# 5VAC-DC.net
KiCad netlist of a schematic drawn in EAGLE
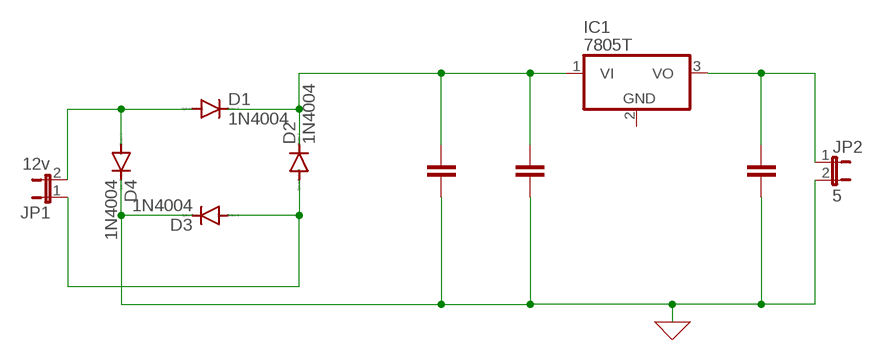
[diagram p0: schematic, sheet 1]

(export (version "E")
  (design (tool "Eeschema 10.0.6"))
  (components
    (comp (ref "D1")
      (value "1N4004")
      (footprint "eagle-import:DO41-10")
      (libsource (lib "eagle-import") (part "1N4004"))
    )
    (comp (ref "D2")
      (value "1N4004")
      (footprint "eagle-import:DO41-10")
      (libsource (lib "eagle-import") (part "1N4004"))
    )
    (comp (ref "D3")
      (value "1N4004")
      (footprint "eagle-import:DO41-10")
      (libsource (lib "eagle-import") (part "1N4004"))
    )
    (comp (ref "D4")
      (value "1N4004")
      (footprint "eagle-import:DO41-10")
      (libsource (lib "eagle-import") (part "1N4004"))
    )
    (comp (ref "IC1")
      (value "7805T")
      (footprint "eagle-import:TO220H")
      (libsource (lib "eagle-import") (part "78T05"))
    )
    (comp (ref "JP1")
      (value "12v")
      (footprint "eagle-import:JP1")
      (libsource (lib "eagle-import") (part "JP1E"))
    )
    (comp (ref "JP2")
      (value "5")
      (footprint "eagle-import:JP1")
      (libsource (lib "eagle-import") (part "JP1E"))
    )
  )
  (nets
    (net (code "1") (name "GND") (class "Default")
      (node (ref "D3") (pin "C") (pinfunction "C_C") (pintype "passive"))
      (node (ref "D4") (pin "C") (pinfunction "C_C") (pintype "passive"))
      (node (ref "JP2") (pin "2") (pinfunction "2_2") (pintype "passive"))
    )
    (net (code "2") (name "Net-(D1-PadA)") (class "Default")
      (node (ref "D1") (pin "A") (pinfunction "A_A") (pintype "passive"))
      (node (ref "D4") (pin "A") (pinfunction "A_A") (pintype "passive"))
      (node (ref "JP1") (pin "2") (pinfunction "2_2") (pintype "passive"))
    )
    (net (code "3") (name "Net-(D2-PadA)") (class "Default")
      (node (ref "D2") (pin "A") (pinfunction "A_A") (pintype "passive"))
      (node (ref "D3") (pin "A") (pinfunction "A_A") (pintype "passive"))
      (node (ref "JP1") (pin "1") (pinfunction "1_1") (pintype "passive"))
    )
    (net (code "4") (name "Net-(IC1-VI)") (class "Default")
      (node (ref "D1") (pin "C") (pinfunction "C_C") (pintype "passive"))
      (node (ref "D2") (pin "C") (pinfunction "C_C") (pintype "passive"))
      (node (ref "IC1") (pin "1") (pinfunction "VI_1") (pintype "input"))
    )
    (net (code "5") (name "Net-(IC1-VO)") (class "Default")
      (node (ref "IC1") (pin "3") (pinfunction "VO_3") (pintype "passive"))
      (node (ref "JP2") (pin "1") (pinfunction "1_1") (pintype "passive"))
    )
    (net (code "6") (name "unconnected-(IC1-GND-Pad2)") (class "Default")
      (node (ref "IC1") (pin "2") (pinfunction "GND_2") (pintype "passive"))
    )
  )
)
